# power_injector_rev_a.net
KiCad netlist of a schematic drawn in EAGLE
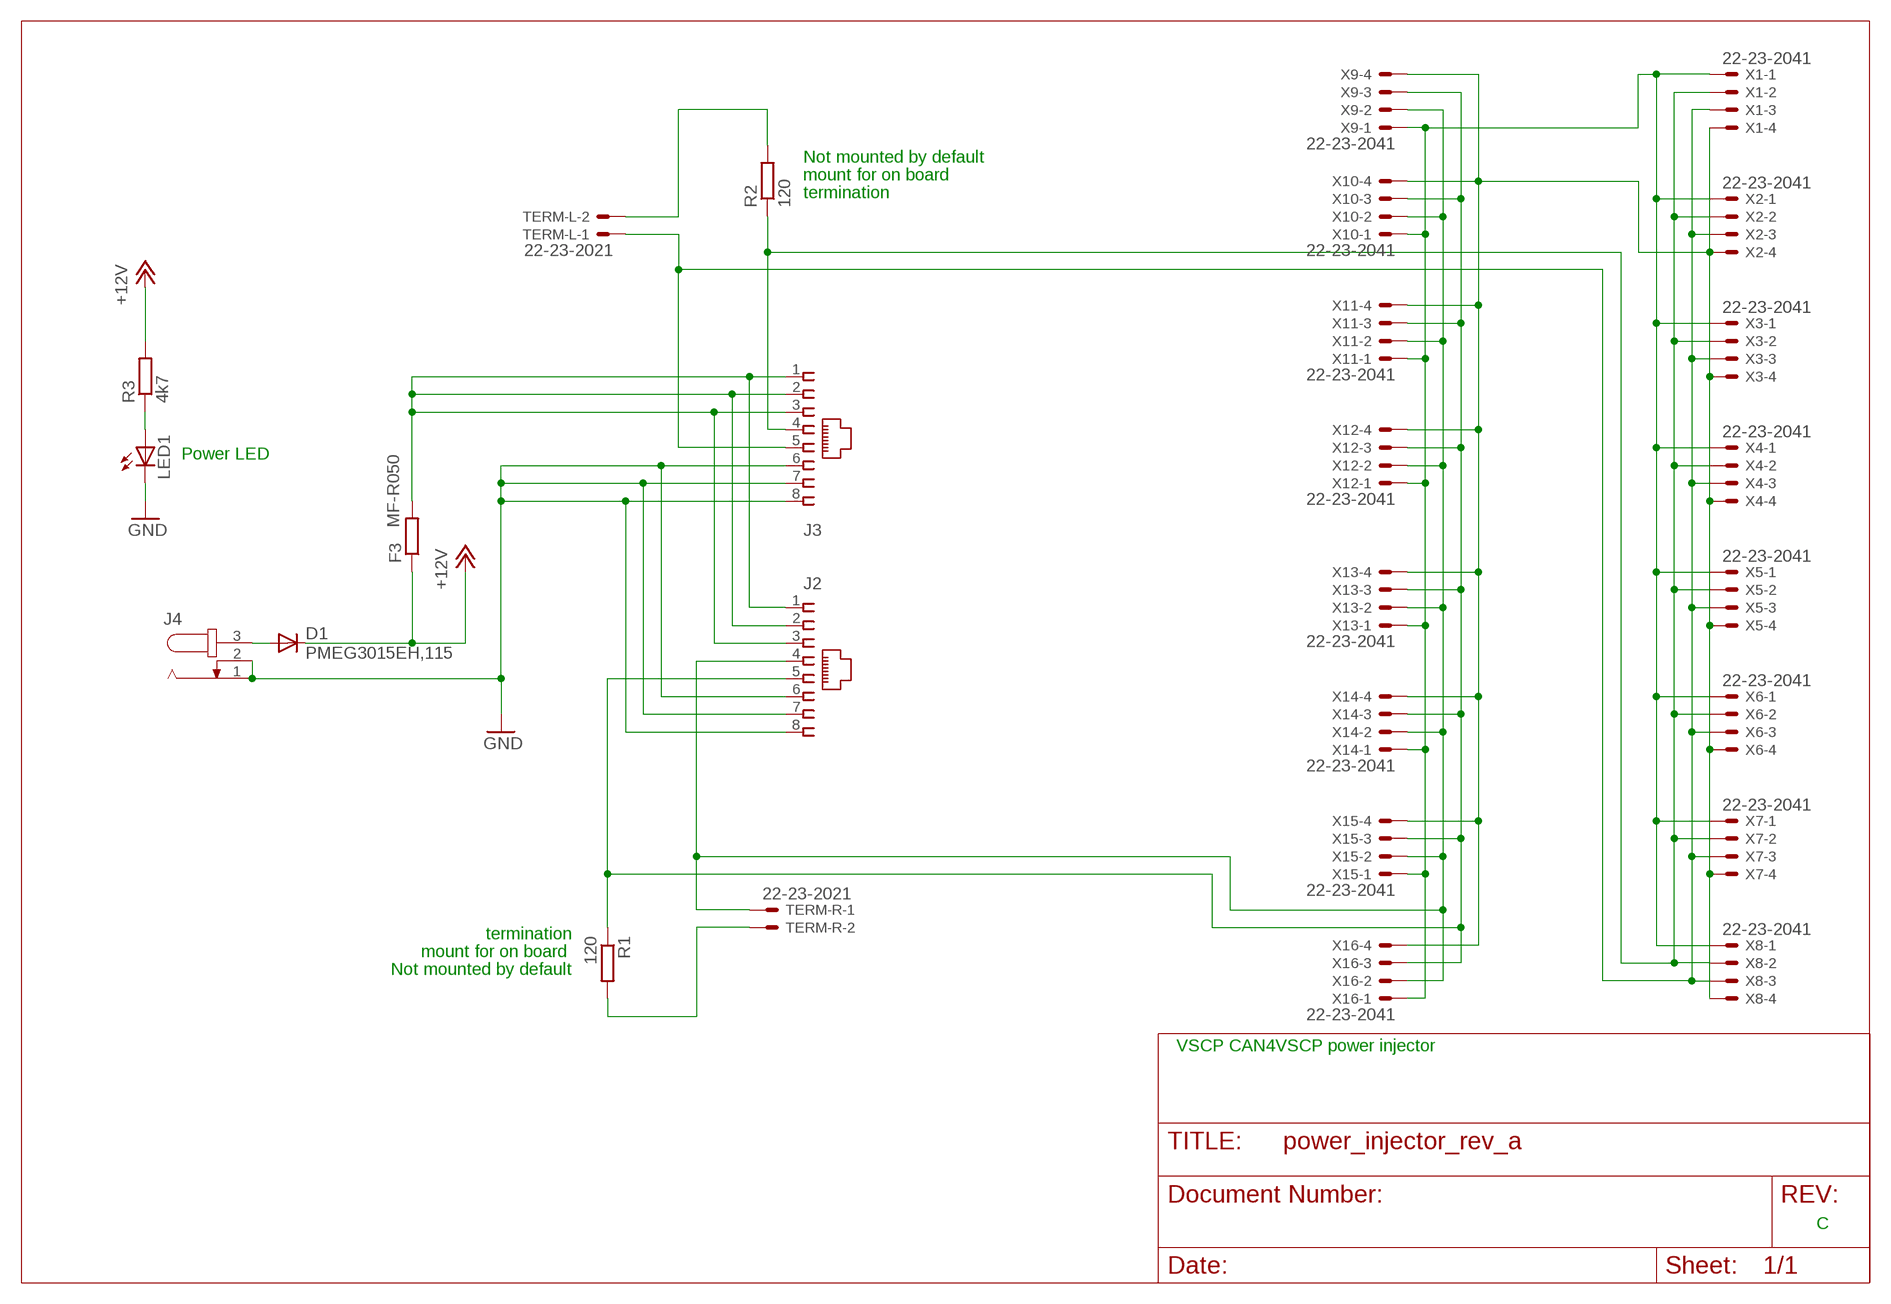
[diagram p0: schematic, sheet 1]

(export (version "E")
  (design (tool "Eeschema 10.0.6"))
  (components
    (comp (ref "D1")
      (value "PMEG3015EH,115")
      (footprint "eagle-import:SMB")
      (libsource (lib "eagle-import") (part "DIODE-SMB"))
    )
    (comp (ref "F3")
      (value "MF-R050")
      (footprint "eagle-import:0204_5")
      (libsource (lib "eagle-import") (part "R-EU_0204/5"))
    )
    (comp (ref "J2")
      (value "A00-108-220-450")
      (footprint "eagle-import:RJ-45")
      (libsource (lib "eagle-import") (part "A00-108-220-450"))
    )
    (comp (ref "J3")
      (value "A00-108-220-450")
      (footprint "eagle-import:RJ-45")
      (libsource (lib "eagle-import") (part "A00-108-220-450"))
    )
    (comp (ref "J4")
      (value "JACK-PLUG0")
      (footprint "eagle-import:SPC4077")
      (libsource (lib "eagle-import") (part "JACK-PLUG0"))
    )
    (comp (ref "LED1")
      (value "LEDCHIP-LED0805")
      (footprint "eagle-import:CHIP-LED0805")
      (libsource (lib "eagle-import") (part "LEDCHIP-LED0805"))
    )
    (comp (ref "R1")
      (value "120")
      (footprint "eagle-import:R0805")
      (libsource (lib "eagle-import") (part "R-EU_R0805"))
    )
    (comp (ref "R2")
      (value "120")
      (footprint "eagle-import:R0805")
      (libsource (lib "eagle-import") (part "R-EU_R0805"))
    )
    (comp (ref "R3")
      (value "4k7")
      (footprint "eagle-import:R0805")
      (libsource (lib "eagle-import") (part "R-EU_R0805"))
    )
    (comp (ref "TERM-L")
      (value "22-23-2021")
      (footprint "eagle-import:22-23-2021")
      (fields (field (name "MF") "MOLEX"))
      (libsource (lib "eagle-import") (part "22-23-2021"))
    )
    (comp (ref "TERM-R")
      (value "22-23-2021")
      (footprint "eagle-import:22-23-2021")
      (fields (field (name "MF") "MOLEX"))
      (libsource (lib "eagle-import") (part "22-23-2021"))
    )
    (comp (ref "X1")
      (value "22-23-2041")
      (footprint "eagle-import:22-23-2041")
      (fields (field (name "MF") "MOLEX"))
      (libsource (lib "eagle-import") (part "22-23-2041"))
    )
    (comp (ref "X2")
      (value "22-23-2041")
      (footprint "eagle-import:22-23-2041")
      (fields (field (name "MF") "MOLEX"))
      (libsource (lib "eagle-import") (part "22-23-2041"))
    )
    (comp (ref "X3")
      (value "22-23-2041")
      (footprint "eagle-import:22-23-2041")
      (fields (field (name "MF") "MOLEX"))
      (libsource (lib "eagle-import") (part "22-23-2041"))
    )
    (comp (ref "X4")
      (value "22-23-2041")
      (footprint "eagle-import:22-23-2041")
      (fields (field (name "MF") "MOLEX"))
      (libsource (lib "eagle-import") (part "22-23-2041"))
    )
    (comp (ref "X5")
      (value "22-23-2041")
      (footprint "eagle-import:22-23-2041")
      (fields (field (name "MF") "MOLEX"))
      (libsource (lib "eagle-import") (part "22-23-2041"))
    )
    (comp (ref "X6")
      (value "22-23-2041")
      (footprint "eagle-import:22-23-2041")
      (fields (field (name "MF") "MOLEX"))
      (libsource (lib "eagle-import") (part "22-23-2041"))
    )
    (comp (ref "X7")
      (value "22-23-2041")
      (footprint "eagle-import:22-23-2041")
      (fields (field (name "MF") "MOLEX"))
      (libsource (lib "eagle-import") (part "22-23-2041"))
    )
    (comp (ref "X8")
      (value "22-23-2041")
      (footprint "eagle-import:22-23-2041")
      (fields (field (name "MF") "MOLEX"))
      (libsource (lib "eagle-import") (part "22-23-2041"))
    )
    (comp (ref "X9")
      (value "22-23-2041")
      (footprint "eagle-import:22-23-2041")
      (fields (field (name "MF") "MOLEX"))
      (libsource (lib "eagle-import") (part "22-23-2041"))
    )
    (comp (ref "X10")
      (value "22-23-2041")
      (footprint "eagle-import:22-23-2041")
      (fields (field (name "MF") "MOLEX"))
      (libsource (lib "eagle-import") (part "22-23-2041"))
    )
    (comp (ref "X11")
      (value "22-23-2041")
      (footprint "eagle-import:22-23-2041")
      (fields (field (name "MF") "MOLEX"))
      (libsource (lib "eagle-import") (part "22-23-2041"))
    )
    (comp (ref "X12")
      (value "22-23-2041")
      (footprint "eagle-import:22-23-2041")
      (fields (field (name "MF") "MOLEX"))
      (libsource (lib "eagle-import") (part "22-23-2041"))
    )
    (comp (ref "X13")
      (value "22-23-2041")
      (footprint "eagle-import:22-23-2041")
      (fields (field (name "MF") "MOLEX"))
      (libsource (lib "eagle-import") (part "22-23-2041"))
    )
    (comp (ref "X14")
      (value "22-23-2041")
      (footprint "eagle-import:22-23-2041")
      (fields (field (name "MF") "MOLEX"))
      (libsource (lib "eagle-import") (part "22-23-2041"))
    )
    (comp (ref "X15")
      (value "22-23-2041")
      (footprint "eagle-import:22-23-2041")
      (fields (field (name "MF") "MOLEX"))
      (libsource (lib "eagle-import") (part "22-23-2041"))
    )
    (comp (ref "X16")
      (value "22-23-2041")
      (footprint "eagle-import:22-23-2041")
      (fields (field (name "MF") "MOLEX"))
      (libsource (lib "eagle-import") (part "22-23-2041"))
    )
  )
  (nets
    (net (code "1") (name "+12V") (class "Default")
      (node (ref "D1") (pin "C") (pinfunction "C_C") (pintype "passive"))
      (node (ref "F3") (pin "1") (pinfunction "1_1") (pintype "passive"))
      (node (ref "R3") (pin "2") (pinfunction "2_2") (pintype "passive"))
    )
    (net (code "2") (name "/CANH") (class "Default")
      (node (ref "J2") (pin "4") (pinfunction "4_4") (pintype "passive"))
      (node (ref "J3") (pin "4") (pinfunction "4_4") (pintype "passive"))
      (node (ref "R2") (pin "1") (pinfunction "1_1") (pintype "passive"))
      (node (ref "TERM-R") (pin "1") (pinfunction "S_1") (pintype "passive"))
      (node (ref "X1") (pin "2") (pinfunction "S_2") (pintype "passive"))
      (node (ref "X10") (pin "2") (pinfunction "S_2") (pintype "passive"))
      (node (ref "X11") (pin "2") (pinfunction "S_2") (pintype "passive"))
      (node (ref "X12") (pin "2") (pinfunction "S_2") (pintype "passive"))
      (node (ref "X13") (pin "2") (pinfunction "S_2") (pintype "passive"))
      (node (ref "X14") (pin "2") (pinfunction "S_2") (pintype "passive"))
      (node (ref "X15") (pin "2") (pinfunction "S_2") (pintype "passive"))
      (node (ref "X16") (pin "2") (pinfunction "S_2") (pintype "passive"))
      (node (ref "X2") (pin "2") (pinfunction "S_2") (pintype "passive"))
      (node (ref "X3") (pin "2") (pinfunction "S_2") (pintype "passive"))
      (node (ref "X4") (pin "2") (pinfunction "S_2") (pintype "passive"))
      (node (ref "X5") (pin "2") (pinfunction "S_2") (pintype "passive"))
      (node (ref "X6") (pin "2") (pinfunction "S_2") (pintype "passive"))
      (node (ref "X7") (pin "2") (pinfunction "S_2") (pintype "passive"))
      (node (ref "X8") (pin "2") (pinfunction "S_2") (pintype "passive"))
      (node (ref "X9") (pin "2") (pinfunction "S_2") (pintype "passive"))
    )
    (net (code "3") (name "/CANL") (class "Default")
      (node (ref "J2") (pin "5") (pinfunction "5_5") (pintype "passive"))
      (node (ref "J3") (pin "5") (pinfunction "5_5") (pintype "passive"))
      (node (ref "R1") (pin "1") (pinfunction "1_1") (pintype "passive"))
      (node (ref "TERM-L") (pin "1") (pinfunction "S_1") (pintype "passive"))
      (node (ref "X1") (pin "3") (pinfunction "S_3") (pintype "passive"))
      (node (ref "X10") (pin "3") (pinfunction "S_3") (pintype "passive"))
      (node (ref "X11") (pin "3") (pinfunction "S_3") (pintype "passive"))
      (node (ref "X12") (pin "3") (pinfunction "S_3") (pintype "passive"))
      (node (ref "X13") (pin "3") (pinfunction "S_3") (pintype "passive"))
      (node (ref "X14") (pin "3") (pinfunction "S_3") (pintype "passive"))
      (node (ref "X15") (pin "3") (pinfunction "S_3") (pintype "passive"))
      (node (ref "X16") (pin "3") (pinfunction "S_3") (pintype "passive"))
      (node (ref "X2") (pin "3") (pinfunction "S_3") (pintype "passive"))
      (node (ref "X3") (pin "3") (pinfunction "S_3") (pintype "passive"))
      (node (ref "X4") (pin "3") (pinfunction "S_3") (pintype "passive"))
      (node (ref "X5") (pin "3") (pinfunction "S_3") (pintype "passive"))
      (node (ref "X6") (pin "3") (pinfunction "S_3") (pintype "passive"))
      (node (ref "X7") (pin "3") (pinfunction "S_3") (pintype "passive"))
      (node (ref "X8") (pin "3") (pinfunction "S_3") (pintype "passive"))
      (node (ref "X9") (pin "3") (pinfunction "S_3") (pintype "passive"))
    )
    (net (code "4") (name "/POWER") (class "Default")
      (node (ref "F3") (pin "2") (pinfunction "2_2") (pintype "passive"))
      (node (ref "J2") (pin "1") (pinfunction "1_1") (pintype "passive"))
      (node (ref "J2") (pin "2") (pinfunction "2_2") (pintype "passive"))
      (node (ref "J2") (pin "3") (pinfunction "3_3") (pintype "passive"))
      (node (ref "J3") (pin "1") (pinfunction "1_1") (pintype "passive"))
      (node (ref "J3") (pin "2") (pinfunction "2_2") (pintype "passive"))
      (node (ref "J3") (pin "3") (pinfunction "3_3") (pintype "passive"))
      (node (ref "X1") (pin "1") (pinfunction "S_1") (pintype "passive"))
      (node (ref "X10") (pin "1") (pinfunction "S_1") (pintype "passive"))
      (node (ref "X11") (pin "1") (pinfunction "S_1") (pintype "passive"))
      (node (ref "X12") (pin "1") (pinfunction "S_1") (pintype "passive"))
      (node (ref "X13") (pin "1") (pinfunction "S_1") (pintype "passive"))
      (node (ref "X14") (pin "1") (pinfunction "S_1") (pintype "passive"))
      (node (ref "X15") (pin "1") (pinfunction "S_1") (pintype "passive"))
      (node (ref "X16") (pin "1") (pinfunction "S_1") (pintype "passive"))
      (node (ref "X2") (pin "1") (pinfunction "S_1") (pintype "passive"))
      (node (ref "X3") (pin "1") (pinfunction "S_1") (pintype "passive"))
      (node (ref "X4") (pin "1") (pinfunction "S_1") (pintype "passive"))
      (node (ref "X5") (pin "1") (pinfunction "S_1") (pintype "passive"))
      (node (ref "X6") (pin "1") (pinfunction "S_1") (pintype "passive"))
      (node (ref "X7") (pin "1") (pinfunction "S_1") (pintype "passive"))
      (node (ref "X8") (pin "1") (pinfunction "S_1") (pintype "passive"))
      (node (ref "X9") (pin "1") (pinfunction "S_1") (pintype "passive"))
    )
    (net (code "5") (name "GND") (class "Default")
      (node (ref "J2") (pin "6") (pinfunction "6_6") (pintype "passive"))
      (node (ref "J2") (pin "7") (pinfunction "7_7") (pintype "passive"))
      (node (ref "J2") (pin "8") (pinfunction "8_8") (pintype "passive"))
      (node (ref "J3") (pin "6") (pinfunction "6_6") (pintype "passive"))
      (node (ref "J3") (pin "7") (pinfunction "7_7") (pintype "passive"))
      (node (ref "J3") (pin "8") (pinfunction "8_8") (pintype "passive"))
      (node (ref "J4") (pin "1") (pinfunction "1_1") (pintype "passive"))
      (node (ref "J4") (pin "2") (pinfunction "2_2") (pintype "passive"))
      (node (ref "LED1") (pin "C") (pinfunction "C_C") (pintype "passive"))
      (node (ref "X1") (pin "4") (pinfunction "S_4") (pintype "passive"))
      (node (ref "X10") (pin "4") (pinfunction "S_4") (pintype "passive"))
      (node (ref "X11") (pin "4") (pinfunction "S_4") (pintype "passive"))
      (node (ref "X12") (pin "4") (pinfunction "S_4") (pintype "passive"))
      (node (ref "X13") (pin "4") (pinfunction "S_4") (pintype "passive"))
      (node (ref "X14") (pin "4") (pinfunction "S_4") (pintype "passive"))
      (node (ref "X15") (pin "4") (pinfunction "S_4") (pintype "passive"))
      (node (ref "X16") (pin "4") (pinfunction "S_4") (pintype "passive"))
      (node (ref "X2") (pin "4") (pinfunction "S_4") (pintype "passive"))
      (node (ref "X3") (pin "4") (pinfunction "S_4") (pintype "passive"))
      (node (ref "X4") (pin "4") (pinfunction "S_4") (pintype "passive"))
      (node (ref "X5") (pin "4") (pinfunction "S_4") (pintype "passive"))
      (node (ref "X6") (pin "4") (pinfunction "S_4") (pintype "passive"))
      (node (ref "X7") (pin "4") (pinfunction "S_4") (pintype "passive"))
      (node (ref "X8") (pin "4") (pinfunction "S_4") (pintype "passive"))
      (node (ref "X9") (pin "4") (pinfunction "S_4") (pintype "passive"))
    )
    (net (code "6") (name "Net-(D1-PadA)") (class "Default")
      (node (ref "D1") (pin "A") (pinfunction "A_A") (pintype "passive"))
      (node (ref "J4") (pin "3") (pinfunction "3_3") (pintype "passive"))
    )
    (net (code "7") (name "Net-(LED1-PadA)") (class "Default")
      (node (ref "LED1") (pin "A") (pinfunction "A_A") (pintype "passive"))
      (node (ref "R3") (pin "1") (pinfunction "1_1") (pintype "passive"))
    )
    (net (code "8") (name "Net-(TERM-LB-S)") (class "Default")
      (node (ref "R2") (pin "2") (pinfunction "2_2") (pintype "passive"))
      (node (ref "TERM-L") (pin "2") (pinfunction "S_2") (pintype "passive"))
    )
    (net (code "9") (name "Net-(TERM-RB-S)") (class "Default")
      (node (ref "R1") (pin "2") (pinfunction "2_2") (pintype "passive"))
      (node (ref "TERM-R") (pin "2") (pinfunction "S_2") (pintype "passive"))
    )
  )
)
